# PDU_Schematic.net
KiCad netlist of a schematic drawn in Altium Designer
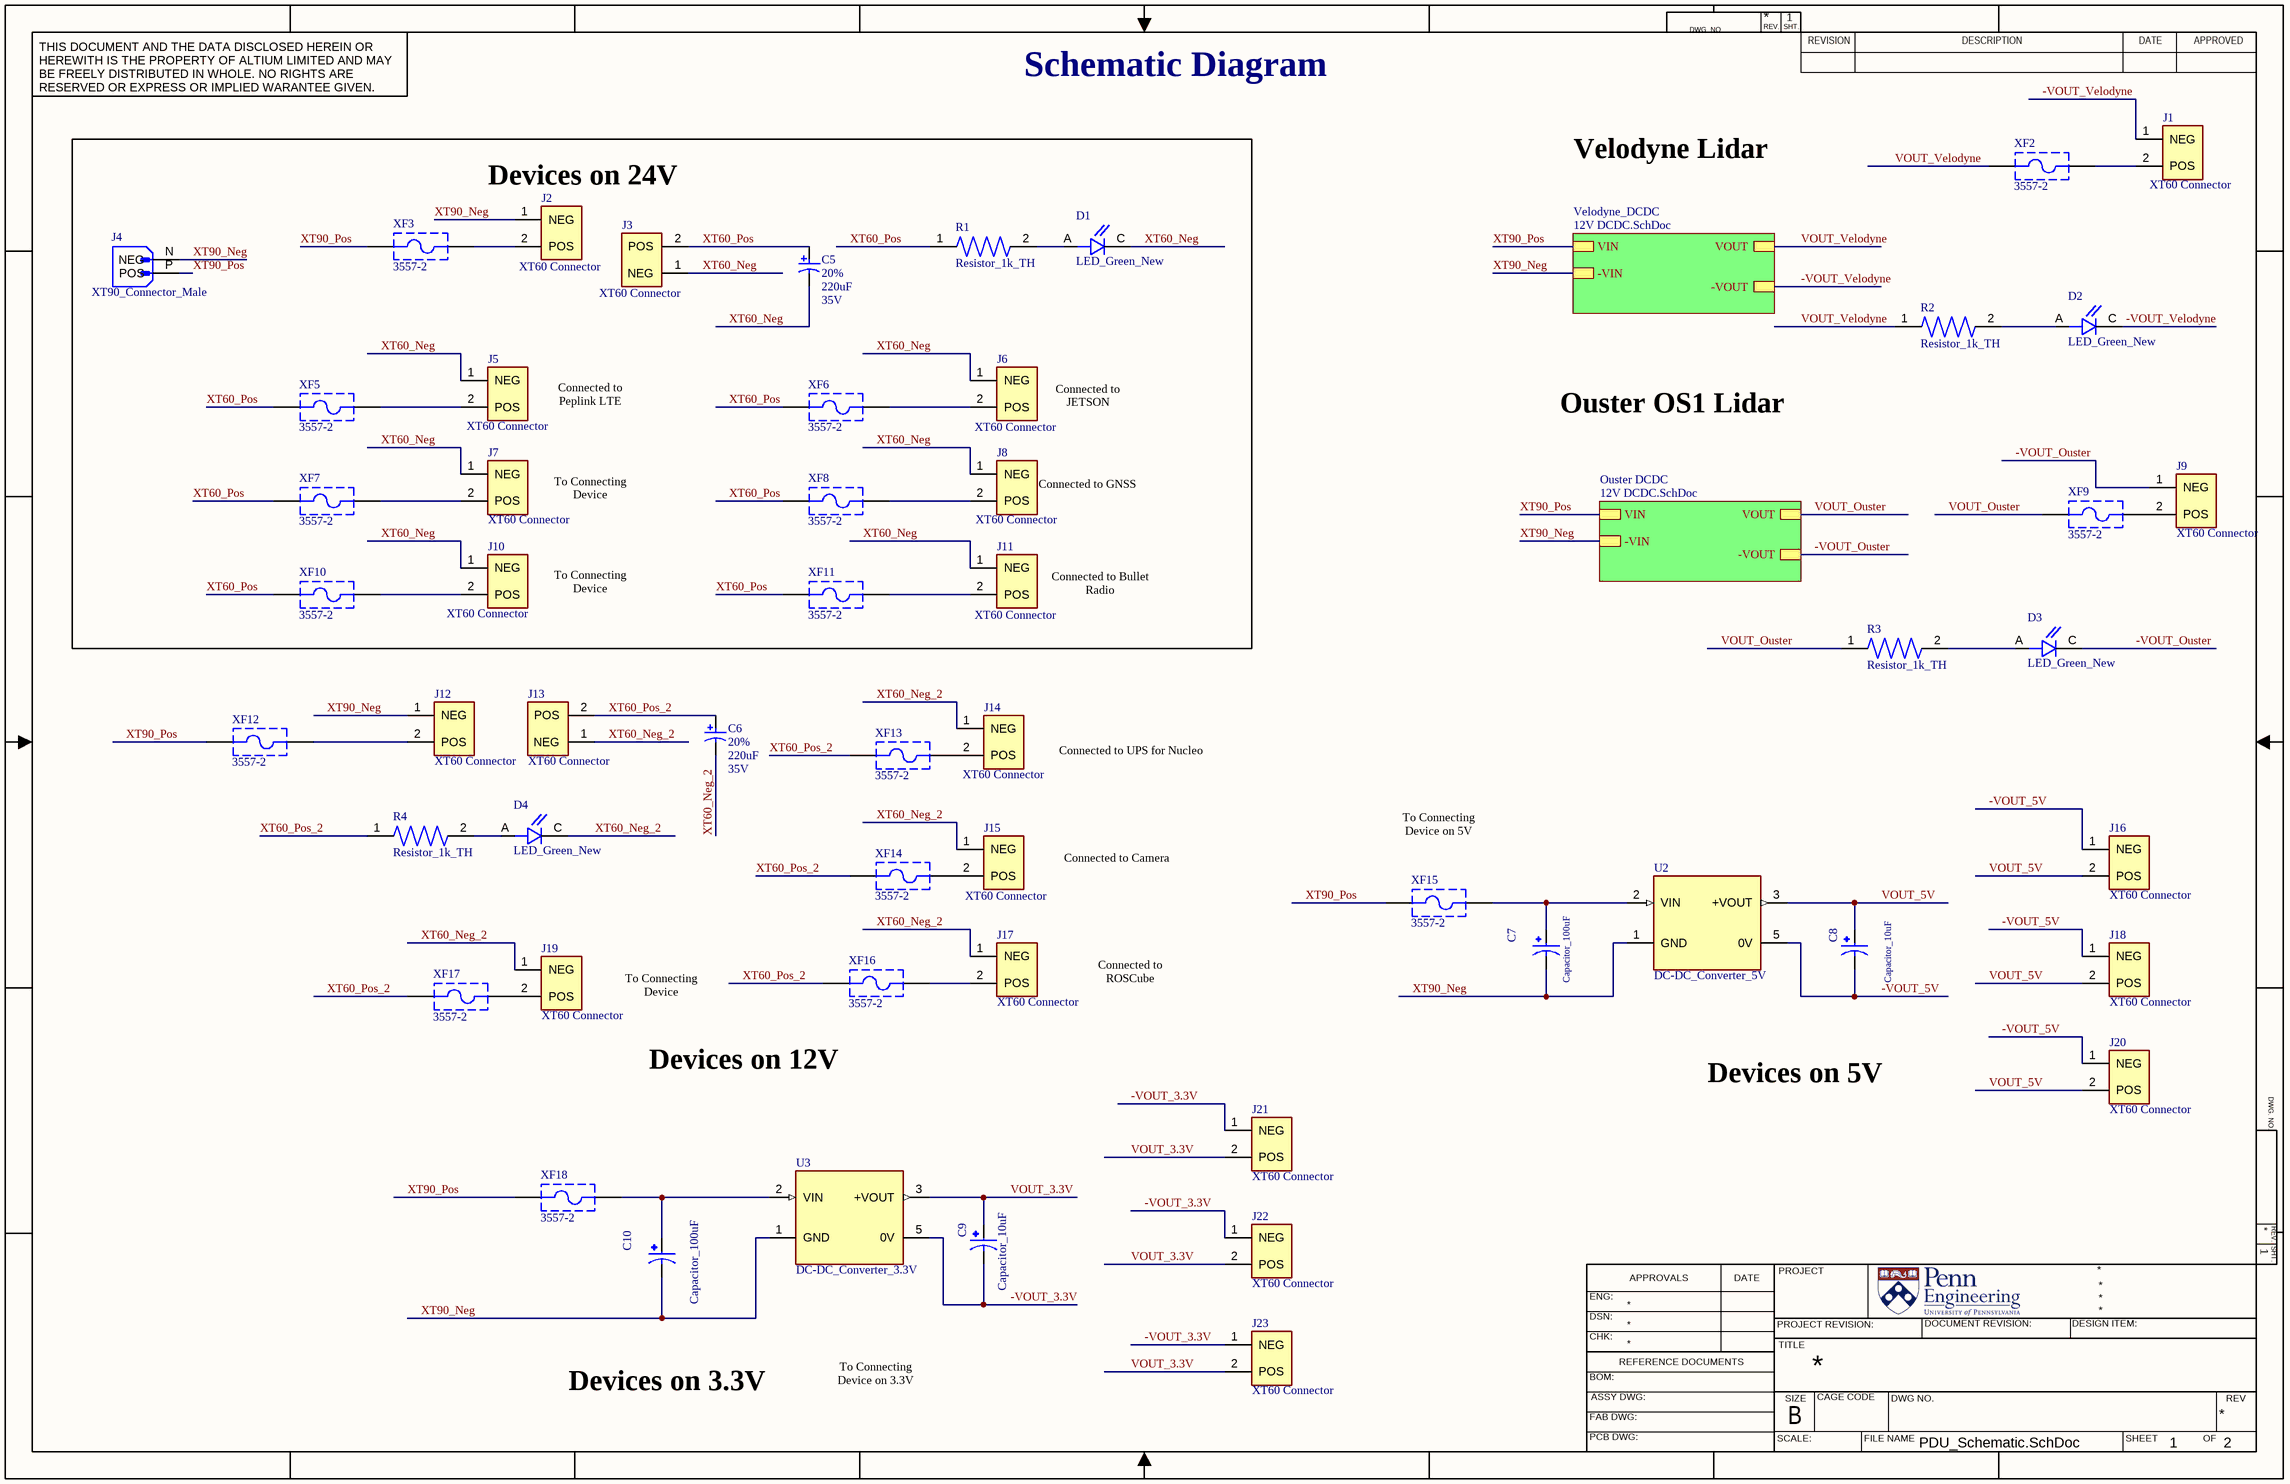
[diagram p0: PDU_Schematic.SchDoc]

(export (version "E")
  (design (tool "Eeschema 10.0.6"))
  (components
    (comp (ref "C5")
      (value "220uF")
      (footprint "NicCap_10x12.5")
      (fields
        (field (name "TOLERANCE") "20%")
        (field (name "VOLTAGE") "35V")
        (field (name "Comment") "ESC227M035AH1AA")
      )
      (libsource (lib "ESE)") (part "NIC-CAP-P-2"))
    )
    (comp (ref "C6")
      (value "220uF")
      (footprint "NicCap_10x12.5")
      (fields
        (field (name "TOLERANCE") "20%")
        (field (name "VOLTAGE") "35V")
        (field (name "Comment") "ESC227M035AH1AA")
      )
      (libsource (lib "ESE)") (part "NIC-CAP-P-2"))
    )
    (comp (ref "C7")
      (value "Capacitor_100uF")
      (footprint "Capacitor_100uF")
      (description "Cap Aluminum Lytic 100uF 16V 20% (5 X 11mm) Radial 5mm 180mA 2000h 85C Automotive Ammo")
      (fields
        (field (name "MANUFACTURER") "Panasonic")
        (field (name "MANUFACTURER PART NUMBER") "ECA-1CM101B")
      )
      (libsource (lib "Schlib1") (part "Capacitor_100uF"))
    )
    (comp (ref "C8")
      (value "Capacitor_10uF")
      (footprint "Capacitor_10uF")
      (description "Cap Aluminum 10uF 50V 20% (6.3 X 5mm) Radial 2.5mm 35mA 1000 hr 85°C Bulk")
      (fields
        (field (name "MANUFACTURER") "Panasonic")
        (field (name "MANUFACTURER PART NUMBER") "ECE-A1HKS100")
      )
      (libsource (lib "Schlib1") (part "Capacitor_10uF"))
    )
    (comp (ref "C9")
      (value "Capacitor_10uF")
      (footprint "Capacitor_10uF")
      (description "Cap Aluminum 10uF 50V 20% (6.3 X 5mm) Radial 2.5mm 35mA 1000 hr 85°C Bulk")
      (fields
        (field (name "MANUFACTURER") "Panasonic")
        (field (name "MANUFACTURER PART NUMBER") "ECE-A1HKS100")
      )
      (libsource (lib "Schlib1") (part "Capacitor_10uF"))
    )
    (comp (ref "C10")
      (value "Capacitor_100uF")
      (footprint "Capacitor_100uF")
      (description "Cap Aluminum Lytic 100uF 16V 20% (5 X 11mm) Radial 5mm 180mA 2000h 85C Automotive Ammo")
      (fields
        (field (name "MANUFACTURER") "Panasonic")
        (field (name "MANUFACTURER PART NUMBER") "ECA-1CM101B")
      )
      (libsource (lib "Schlib1") (part "Capacitor_100uF"))
    )
    (comp (ref "D1")
      (value "LED_Green_New")
      (footprint "LED_Green_New")
      (description "White high-intensity LED lamp, Color White, Vf 3.2 V, Radial-2, RoHS")
      (fields (field (name "MANUFACTURER") "TT Optek") (field (name "MANUFACTURER PART NUMBER") "OVLAW4CB7"))
      (libsource (lib "Schlib1") (part "LED_Green_New"))
    )
    (comp (ref "D2")
      (value "LED_Green_New")
      (footprint "LED_Green_New")
      (description "White high-intensity LED lamp, Color White, Vf 3.2 V, Radial-2, RoHS")
      (fields (field (name "MANUFACTURER") "TT Optek") (field (name "MANUFACTURER PART NUMBER") "OVLAW4CB7"))
      (libsource (lib "Schlib1") (part "LED_Green_New"))
    )
    (comp (ref "D3")
      (value "LED_Green_New")
      (footprint "LED_Green_New")
      (description "White high-intensity LED lamp, Color White, Vf 3.2 V, Radial-2, RoHS")
      (fields (field (name "MANUFACTURER") "TT Optek") (field (name "MANUFACTURER PART NUMBER") "OVLAW4CB7"))
      (libsource (lib "Schlib1") (part "LED_Green_New"))
    )
    (comp (ref "D4")
      (value "LED_Green_New")
      (footprint "LED_Green_New")
      (description "White high-intensity LED lamp, Color White, Vf 3.2 V, Radial-2, RoHS")
      (fields (field (name "MANUFACTURER") "TT Optek") (field (name "MANUFACTURER PART NUMBER") "OVLAW4CB7"))
      (libsource (lib "Schlib1") (part "LED_Green_New"))
    )
    (comp (ref "J1")
      (value "XT60 Connector")
      (footprint "XT60_Connector")
      (description "DC power connectors AMASS - XT60")
      (libsource (lib "Schlib1") (part "XT60 Connector"))
    )
    (comp (ref "J2")
      (value "XT60 Connector")
      (footprint "XT60_Connector")
      (description "DC power connectors AMASS - XT60")
      (libsource (lib "Schlib1") (part "XT60 Connector"))
    )
    (comp (ref "J3")
      (value "XT60 Connector")
      (footprint "XT60_Connector")
      (description "DC power connectors AMASS - XT60")
      (libsource (lib "") (part "XT60 Connector_1"))
    )
    (comp (ref "J4")
      (value "XT90_Connector_Male")
      (footprint "XT90_Connector_Male")
      (description "DC power connectors AMASS - XT90")
      (libsource (lib "Schlib1") (part "XT90_Connector_Male"))
    )
    (comp (ref "J5")
      (value "XT60 Connector")
      (footprint "XT60_Connector")
      (description "DC power connectors AMASS - XT60")
      (libsource (lib "Schlib1") (part "XT60 Connector"))
    )
    (comp (ref "J6")
      (value "XT60 Connector")
      (footprint "XT60_Connector")
      (description "DC power connectors AMASS - XT60")
      (libsource (lib "Schlib1") (part "XT60 Connector"))
    )
    (comp (ref "J7")
      (value "XT60 Connector")
      (footprint "XT60_Connector")
      (description "DC power connectors AMASS - XT60")
      (libsource (lib "Schlib1") (part "XT60 Connector"))
    )
    (comp (ref "J8")
      (value "XT60 Connector")
      (footprint "XT60_Connector")
      (description "DC power connectors AMASS - XT60")
      (libsource (lib "Schlib1") (part "XT60 Connector"))
    )
    (comp (ref "J9")
      (value "XT60 Connector")
      (footprint "XT60_Connector")
      (description "DC power connectors AMASS - XT60")
      (libsource (lib "Schlib1") (part "XT60 Connector"))
    )
    (comp (ref "J10")
      (value "XT60 Connector")
      (footprint "XT60_Connector")
      (description "DC power connectors AMASS - XT60")
      (libsource (lib "Schlib1") (part "XT60 Connector"))
    )
    (comp (ref "J11")
      (value "XT60 Connector")
      (footprint "XT60_Connector")
      (description "DC power connectors AMASS - XT60")
      (libsource (lib "Schlib1") (part "XT60 Connector"))
    )
    (comp (ref "J12")
      (value "XT60 Connector")
      (footprint "XT60_Connector")
      (description "DC power connectors AMASS - XT60")
      (libsource (lib "Schlib1") (part "XT60 Connector"))
    )
    (comp (ref "J13")
      (value "XT60 Connector")
      (footprint "XT60_Connector")
      (description "DC power connectors AMASS - XT60")
      (libsource (lib "") (part "XT60 Connector_1"))
    )
    (comp (ref "J14")
      (value "XT60 Connector")
      (footprint "XT60_Connector")
      (description "DC power connectors AMASS - XT60")
      (libsource (lib "Schlib1") (part "XT60 Connector"))
    )
    (comp (ref "J15")
      (value "XT60 Connector")
      (footprint "XT60_Connector")
      (description "DC power connectors AMASS - XT60")
      (libsource (lib "Schlib1") (part "XT60 Connector"))
    )
    (comp (ref "J16")
      (value "XT60 Connector")
      (footprint "XT60_Connector")
      (description "DC power connectors AMASS - XT60")
      (libsource (lib "Schlib1") (part "XT60 Connector"))
    )
    (comp (ref "J17")
      (value "XT60 Connector")
      (footprint "XT60_Connector")
      (description "DC power connectors AMASS - XT60")
      (libsource (lib "Schlib1") (part "XT60 Connector"))
    )
    (comp (ref "J18")
      (value "XT60 Connector")
      (footprint "XT60_Connector")
      (description "DC power connectors AMASS - XT60")
      (libsource (lib "Schlib1") (part "XT60 Connector"))
    )
    (comp (ref "J19")
      (value "XT60 Connector")
      (footprint "XT60_Connector")
      (description "DC power connectors AMASS - XT60")
      (libsource (lib "Schlib1") (part "XT60 Connector"))
    )
    (comp (ref "J20")
      (value "XT60 Connector")
      (footprint "XT60_Connector")
      (description "DC power connectors AMASS - XT60")
      (libsource (lib "Schlib1") (part "XT60 Connector"))
    )
    (comp (ref "J21")
      (value "XT60 Connector")
      (footprint "XT60_Connector")
      (description "DC power connectors AMASS - XT60")
      (libsource (lib "Schlib1") (part "XT60 Connector"))
    )
    (comp (ref "J22")
      (value "XT60 Connector")
      (footprint "XT60_Connector")
      (description "DC power connectors AMASS - XT60")
      (libsource (lib "Schlib1") (part "XT60 Connector"))
    )
    (comp (ref "J23")
      (value "XT60 Connector")
      (footprint "XT60_Connector")
      (description "DC power connectors AMASS - XT60")
      (libsource (lib "Schlib1") (part "XT60 Connector"))
    )
    (comp (ref "R1")
      (value "Resistor_1k_TH")
      (footprint "Resistor_1k_TH")
      (description "Carbon Film Resistors - Through Hole 1K Ohm 5% 1/4W Res Carbon Film")
      (fields
        (field (name "MANUFACTURER") "TE Connectivity")
        (field (name "MANUFACTURER PART NUMBER") "2-1623927-3")
      )
      (libsource (lib "Schlib1") (part "Resistor_1k_TH"))
    )
    (comp (ref "R2")
      (value "Resistor_1k_TH")
      (footprint "Resistor_1k_TH")
      (description "Carbon Film Resistors - Through Hole 1K Ohm 5% 1/4W Res Carbon Film")
      (fields
        (field (name "MANUFACTURER") "TE Connectivity")
        (field (name "MANUFACTURER PART NUMBER") "2-1623927-3")
      )
      (libsource (lib "Schlib1") (part "Resistor_1k_TH"))
    )
    (comp (ref "R3")
      (value "Resistor_1k_TH")
      (footprint "Resistor_1k_TH")
      (description "Carbon Film Resistors - Through Hole 1K Ohm 5% 1/4W Res Carbon Film")
      (fields
        (field (name "MANUFACTURER") "TE Connectivity")
        (field (name "MANUFACTURER PART NUMBER") "2-1623927-3")
      )
      (libsource (lib "Schlib1") (part "Resistor_1k_TH"))
    )
    (comp (ref "R4")
      (value "Resistor_1k_TH")
      (footprint "Resistor_1k_TH")
      (description "Carbon Film Resistors - Through Hole 1K Ohm 5% 1/4W Res Carbon Film")
      (fields
        (field (name "MANUFACTURER") "TE Connectivity")
        (field (name "MANUFACTURER PART NUMBER") "2-1623927-3")
      )
      (libsource (lib "Schlib1") (part "Resistor_1k_TH"))
    )
    (comp (ref "U2")
      (value "DC-DC_Converter_5V")
      (footprint "DC-DC_Converter_5V")
      (description "5 Vdc, 2 A, 10 W, 8 to 36 Vdc Input Range")
      (fields (field (name "MANUFACTURER") "CUI") (field (name "MANUFACTURER PART NUMBER") "P7805-2000R-S"))
      (libsource (lib "Schlib1") (part "DC-DC_Converter_5V"))
    )
    (comp (ref "U3")
      (value "DC-DC_Converter_3.3V")
      (footprint "DC-DC_Converter_3.3V")
      (description "3.3 Vdc, 2 A, 6.6 W, 6 to 36 Vdc Input Range")
      (fields (field (name "MANUFACTURER") "CUI") (field (name "MANUFACTURER PART NUMBER") "P7803-2000R-S"))
      (libsource (lib "Schlib1") (part "DC-DC_Converter_3.3V"))
    )
    (comp (ref "XF2")
      (value "3557-2")
      (footprint "KSTN-3557-2")
      (description "Fuse Holder; Auto; 2 in1 Blade; THM; 1 Fuse; Vertical; 30 Amps; ATO/ATC")
      (libsource (lib "ESE)") (part "FUSE_HOLDER-4"))
    )
    (comp (ref "XF3")
      (value "3557-2")
      (footprint "KSTN-3557-2")
      (description "Fuse Holder; Auto; 2 in1 Blade; THM; 1 Fuse; Vertical; 30 Amps; ATO/ATC")
      (libsource (lib "ESE)") (part "FUSE_HOLDER-4"))
    )
    (comp (ref "XF5")
      (value "3557-2")
      (footprint "KSTN-3557-2")
      (description "Fuse Holder; Auto; 2 in1 Blade; THM; 1 Fuse; Vertical; 30 Amps; ATO/ATC")
      (libsource (lib "ESE)") (part "FUSE_HOLDER-4"))
    )
    (comp (ref "XF6")
      (value "3557-2")
      (footprint "KSTN-3557-2")
      (description "Fuse Holder; Auto; 2 in1 Blade; THM; 1 Fuse; Vertical; 30 Amps; ATO/ATC")
      (libsource (lib "ESE)") (part "FUSE_HOLDER-4"))
    )
    (comp (ref "XF7")
      (value "3557-2")
      (footprint "KSTN-3557-2")
      (description "Fuse Holder; Auto; 2 in1 Blade; THM; 1 Fuse; Vertical; 30 Amps; ATO/ATC")
      (libsource (lib "ESE)") (part "FUSE_HOLDER-4"))
    )
    (comp (ref "XF8")
      (value "3557-2")
      (footprint "KSTN-3557-2")
      (description "Fuse Holder; Auto; 2 in1 Blade; THM; 1 Fuse; Vertical; 30 Amps; ATO/ATC")
      (libsource (lib "ESE)") (part "FUSE_HOLDER-4"))
    )
    (comp (ref "XF9")
      (value "3557-2")
      (footprint "KSTN-3557-2")
      (description "Fuse Holder; Auto; 2 in1 Blade; THM; 1 Fuse; Vertical; 30 Amps; ATO/ATC")
      (libsource (lib "ESE)") (part "FUSE_HOLDER-4"))
    )
    (comp (ref "XF10")
      (value "3557-2")
      (footprint "KSTN-3557-2")
      (description "Fuse Holder; Auto; 2 in1 Blade; THM; 1 Fuse; Vertical; 30 Amps; ATO/ATC")
      (libsource (lib "ESE)") (part "FUSE_HOLDER-4"))
    )
    (comp (ref "XF11")
      (value "3557-2")
      (footprint "KSTN-3557-2")
      (description "Fuse Holder; Auto; 2 in1 Blade; THM; 1 Fuse; Vertical; 30 Amps; ATO/ATC")
      (libsource (lib "ESE)") (part "FUSE_HOLDER-4"))
    )
    (comp (ref "XF12")
      (value "3557-2")
      (footprint "KSTN-3557-2")
      (description "Fuse Holder; Auto; 2 in1 Blade; THM; 1 Fuse; Vertical; 30 Amps; ATO/ATC")
      (libsource (lib "ESE)") (part "FUSE_HOLDER-4"))
    )
    (comp (ref "XF13")
      (value "3557-2")
      (footprint "KSTN-3557-2")
      (description "Fuse Holder; Auto; 2 in1 Blade; THM; 1 Fuse; Vertical; 30 Amps; ATO/ATC")
      (libsource (lib "ESE)") (part "FUSE_HOLDER-4"))
    )
    (comp (ref "XF14")
      (value "3557-2")
      (footprint "KSTN-3557-2")
      (description "Fuse Holder; Auto; 2 in1 Blade; THM; 1 Fuse; Vertical; 30 Amps; ATO/ATC")
      (libsource (lib "ESE)") (part "FUSE_HOLDER-4"))
    )
    (comp (ref "XF15")
      (value "3557-2")
      (footprint "KSTN-3557-2")
      (description "Fuse Holder; Auto; 2 in1 Blade; THM; 1 Fuse; Vertical; 30 Amps; ATO/ATC")
      (libsource (lib "University of Pennsylvania (SEAS)") (part "FUSE_HOLDER-4"))
    )
    (comp (ref "XF16")
      (value "3557-2")
      (footprint "KSTN-3557-2")
      (description "Fuse Holder; Auto; 2 in1 Blade; THM; 1 Fuse; Vertical; 30 Amps; ATO/ATC")
      (libsource (lib "University of Pennsylvania (SEAS)") (part "FUSE_HOLDER-4"))
    )
    (comp (ref "XF17")
      (value "3557-2")
      (footprint "KSTN-3557-2")
      (description "Fuse Holder; Auto; 2 in1 Blade; THM; 1 Fuse; Vertical; 30 Amps; ATO/ATC")
      (libsource (lib "ESE)") (part "FUSE_HOLDER-4"))
    )
    (comp (ref "XF18")
      (value "3557-2")
      (footprint "KSTN-3557-2")
      (description "Fuse Holder; Auto; 2 in1 Blade; THM; 1 Fuse; Vertical; 30 Amps; ATO/ATC")
      (libsource (lib "University of Pennsylvania (SEAS)") (part "FUSE_HOLDER-4"))
    )
  )
  (nets
    (net (code "1") (name "/-VOUT_3.3V") (class "Default")
      (node (ref "C9") (pin "N") (pinfunction "N_N") (pintype "passive"))
      (node (ref "J21") (pin "1") (pinfunction "NEG_1") (pintype "passive"))
      (node (ref "J22") (pin "1") (pinfunction "NEG_1") (pintype "passive"))
      (node (ref "J23") (pin "1") (pinfunction "NEG_1") (pintype "passive"))
      (node (ref "U3") (pin "5") (pinfunction "0V_5") (pintype "power_in"))
    )
    (net (code "2") (name "/-VOUT_5V") (class "Default")
      (node (ref "C8") (pin "N") (pinfunction "N_N") (pintype "passive"))
      (node (ref "J16") (pin "1") (pinfunction "NEG_1") (pintype "passive"))
      (node (ref "J18") (pin "1") (pinfunction "NEG_1") (pintype "passive"))
      (node (ref "J20") (pin "1") (pinfunction "NEG_1") (pintype "passive"))
      (node (ref "U2") (pin "5") (pinfunction "0V_5") (pintype "power_in"))
    )
    (net (code "3") (name "/-VOUT_Ouster") (class "Default")
      (node (ref "D3") (pin "C") (pinfunction "C_C") (pintype "passive"))
      (node (ref "J9") (pin "1") (pinfunction "NEG_1") (pintype "passive"))
    )
    (net (code "4") (name "/-VOUT_Velodyne") (class "Default")
      (node (ref "D2") (pin "C") (pinfunction "C_C") (pintype "passive"))
      (node (ref "J1") (pin "1") (pinfunction "NEG_1") (pintype "passive"))
    )
    (net (code "5") (name "/VOUT_3.3V") (class "Default")
      (node (ref "C9") (pin "P") (pinfunction "P_P") (pintype "passive"))
      (node (ref "J21") (pin "2") (pinfunction "POS_2") (pintype "passive"))
      (node (ref "J22") (pin "2") (pinfunction "POS_2") (pintype "passive"))
      (node (ref "J23") (pin "2") (pinfunction "POS_2") (pintype "passive"))
      (node (ref "U3") (pin "3") (pinfunction "+VOUT_3") (pintype "output"))
    )
    (net (code "6") (name "/VOUT_5V") (class "Default")
      (node (ref "C8") (pin "P") (pinfunction "P_P") (pintype "passive"))
      (node (ref "J16") (pin "2") (pinfunction "POS_2") (pintype "passive"))
      (node (ref "J18") (pin "2") (pinfunction "POS_2") (pintype "passive"))
      (node (ref "J20") (pin "2") (pinfunction "POS_2") (pintype "passive"))
      (node (ref "U2") (pin "3") (pinfunction "+VOUT_3") (pintype "output"))
    )
    (net (code "7") (name "/VOUT_Ouster") (class "Default")
      (node (ref "R3") (pin "1") (pinfunction "1_1") (pintype "passive"))
      (node (ref "XF9") (pin "1") (pinfunction "1_1") (pintype "passive"))
    )
    (net (code "8") (name "/VOUT_Velodyne") (class "Default")
      (node (ref "R2") (pin "1") (pinfunction "1_1") (pintype "passive"))
      (node (ref "XF2") (pin "1") (pinfunction "1_1") (pintype "passive"))
    )
    (net (code "9") (name "/XT60_Neg") (class "Default")
      (node (ref "C5") (pin "2") (pinfunction "2_2") (pintype "passive"))
      (node (ref "D1") (pin "C") (pinfunction "C_C") (pintype "passive"))
      (node (ref "J10") (pin "1") (pinfunction "NEG_1") (pintype "passive"))
      (node (ref "J11") (pin "1") (pinfunction "NEG_1") (pintype "passive"))
      (node (ref "J3") (pin "1") (pinfunction "NEG_1") (pintype "passive"))
      (node (ref "J5") (pin "1") (pinfunction "NEG_1") (pintype "passive"))
      (node (ref "J6") (pin "1") (pinfunction "NEG_1") (pintype "passive"))
      (node (ref "J7") (pin "1") (pinfunction "NEG_1") (pintype "passive"))
      (node (ref "J8") (pin "1") (pinfunction "NEG_1") (pintype "passive"))
    )
    (net (code "10") (name "/XT60_Neg_2") (class "Default")
      (node (ref "C6") (pin "2") (pinfunction "2_2") (pintype "passive"))
      (node (ref "D4") (pin "C") (pinfunction "C_C") (pintype "passive"))
      (node (ref "J13") (pin "1") (pinfunction "NEG_1") (pintype "passive"))
      (node (ref "J14") (pin "1") (pinfunction "NEG_1") (pintype "passive"))
      (node (ref "J15") (pin "1") (pinfunction "NEG_1") (pintype "passive"))
      (node (ref "J17") (pin "1") (pinfunction "NEG_1") (pintype "passive"))
      (node (ref "J19") (pin "1") (pinfunction "NEG_1") (pintype "passive"))
    )
    (net (code "11") (name "/XT60_Pos") (class "Default")
      (node (ref "C5") (pin "1") (pinfunction "1_1") (pintype "passive"))
      (node (ref "J3") (pin "2") (pinfunction "POS_2") (pintype "passive"))
      (node (ref "R1") (pin "1") (pinfunction "1_1") (pintype "passive"))
      (node (ref "XF10") (pin "1") (pinfunction "1_1") (pintype "passive"))
      (node (ref "XF11") (pin "1") (pinfunction "1_1") (pintype "passive"))
      (node (ref "XF5") (pin "1") (pinfunction "1_1") (pintype "passive"))
      (node (ref "XF6") (pin "1") (pinfunction "1_1") (pintype "passive"))
      (node (ref "XF7") (pin "1") (pinfunction "1_1") (pintype "passive"))
      (node (ref "XF8") (pin "1") (pinfunction "1_1") (pintype "passive"))
    )
    (net (code "12") (name "/XT60_Pos_2") (class "Default")
      (node (ref "C6") (pin "1") (pinfunction "1_1") (pintype "passive"))
      (node (ref "J13") (pin "2") (pinfunction "POS_2") (pintype "passive"))
      (node (ref "R4") (pin "1") (pinfunction "1_1") (pintype "passive"))
      (node (ref "XF13") (pin "1") (pinfunction "1_1") (pintype "passive"))
      (node (ref "XF14") (pin "1") (pinfunction "1_1") (pintype "passive"))
      (node (ref "XF16") (pin "1") (pinfunction "1_1") (pintype "passive"))
      (node (ref "XF17") (pin "1") (pinfunction "1_1") (pintype "passive"))
    )
    (net (code "13") (name "/XT90_Neg") (class "Default")
      (node (ref "C10") (pin "N") (pinfunction "N_N") (pintype "passive"))
      (node (ref "C7") (pin "N") (pinfunction "N_N") (pintype "passive"))
      (node (ref "J12") (pin "1") (pinfunction "NEG_1") (pintype "passive"))
      (node (ref "J2") (pin "1") (pinfunction "NEG_1") (pintype "passive"))
      (node (ref "J4") (pin "N") (pinfunction "NEG_N") (pintype "passive"))
      (node (ref "U2") (pin "1") (pinfunction "GND_1") (pintype "power_in"))
      (node (ref "U3") (pin "1") (pinfunction "GND_1") (pintype "power_in"))
    )
    (net (code "14") (name "/XT90_Pos") (class "Default")
      (node (ref "J4") (pin "P") (pinfunction "POS_P") (pintype "passive"))
      (node (ref "XF12") (pin "1") (pinfunction "1_1") (pintype "passive"))
      (node (ref "XF15") (pin "1") (pinfunction "1_1") (pintype "passive"))
      (node (ref "XF18") (pin "1") (pinfunction "1_1") (pintype "passive"))
      (node (ref "XF3") (pin "1") (pinfunction "1_1") (pintype "passive"))
    )
    (net (code "15") (name "Net-(D1-PadA)") (class "Default")
      (node (ref "D1") (pin "A") (pinfunction "A_A") (pintype "passive"))
      (node (ref "R1") (pin "2") (pinfunction "2_2") (pintype "passive"))
    )
    (net (code "16") (name "Net-(D2-PadA)") (class "Default")
      (node (ref "D2") (pin "A") (pinfunction "A_A") (pintype "passive"))
      (node (ref "R2") (pin "2") (pinfunction "2_2") (pintype "passive"))
    )
    (net (code "17") (name "Net-(D3-PadA)") (class "Default")
      (node (ref "D3") (pin "A") (pinfunction "A_A") (pintype "passive"))
      (node (ref "R3") (pin "2") (pinfunction "2_2") (pintype "passive"))
    )
    (net (code "18") (name "Net-(D4-PadA)") (class "Default")
      (node (ref "D4") (pin "A") (pinfunction "A_A") (pintype "passive"))
      (node (ref "R4") (pin "2") (pinfunction "2_2") (pintype "passive"))
    )
    (net (code "19") (name "Net-(J1-POS)") (class "Default")
      (node (ref "J1") (pin "2") (pinfunction "POS_2") (pintype "passive"))
      (node (ref "XF2") (pin "2") (pinfunction "2_2") (pintype "passive"))
    )
    (net (code "20") (name "Net-(J2-POS)") (class "Default")
      (node (ref "J2") (pin "2") (pinfunction "POS_2") (pintype "passive"))
      (node (ref "XF3") (pin "2") (pinfunction "2_2") (pintype "passive"))
    )
    (net (code "21") (name "Net-(J5-POS)") (class "Default")
      (node (ref "J5") (pin "2") (pinfunction "POS_2") (pintype "passive"))
      (node (ref "XF5") (pin "2") (pinfunction "2_2") (pintype "passive"))
    )
    (net (code "22") (name "Net-(J6-POS)") (class "Default")
      (node (ref "J6") (pin "2") (pinfunction "POS_2") (pintype "passive"))
      (node (ref "XF6") (pin "2") (pinfunction "2_2") (pintype "passive"))
    )
    (net (code "23") (name "Net-(J7-POS)") (class "Default")
      (node (ref "J7") (pin "2") (pinfunction "POS_2") (pintype "passive"))
      (node (ref "XF7") (pin "2") (pinfunction "2_2") (pintype "passive"))
    )
    (net (code "24") (name "Net-(J8-POS)") (class "Default")
      (node (ref "J8") (pin "2") (pinfunction "POS_2") (pintype "passive"))
      (node (ref "XF8") (pin "2") (pinfunction "2_2") (pintype "passive"))
    )
    (net (code "25") (name "Net-(J9-POS)") (class "Default")
      (node (ref "J9") (pin "2") (pinfunction "POS_2") (pintype "passive"))
      (node (ref "XF9") (pin "2") (pinfunction "2_2") (pintype "passive"))
    )
    (net (code "26") (name "Net-(J10-POS)") (class "Default")
      (node (ref "J10") (pin "2") (pinfunction "POS_2") (pintype "passive"))
      (node (ref "XF10") (pin "2") (pinfunction "2_2") (pintype "passive"))
    )
    (net (code "27") (name "Net-(J11-POS)") (class "Default")
      (node (ref "J11") (pin "2") (pinfunction "POS_2") (pintype "passive"))
      (node (ref "XF11") (pin "2") (pinfunction "2_2") (pintype "passive"))
    )
    (net (code "28") (name "Net-(J12-POS)") (class "Default")
      (node (ref "J12") (pin "2") (pinfunction "POS_2") (pintype "passive"))
      (node (ref "XF12") (pin "2") (pinfunction "2_2") (pintype "passive"))
    )
    (net (code "29") (name "Net-(J14-POS)") (class "Default")
      (node (ref "J14") (pin "2") (pinfunction "POS_2") (pintype "passive"))
      (node (ref "XF13") (pin "2") (pinfunction "2_2") (pintype "passive"))
    )
    (net (code "30") (name "Net-(J15-POS)") (class "Default")
      (node (ref "J15") (pin "2") (pinfunction "POS_2") (pintype "passive"))
      (node (ref "XF14") (pin "2") (pinfunction "2_2") (pintype "passive"))
    )
    (net (code "31") (name "Net-(J17-POS)") (class "Default")
      (node (ref "J17") (pin "2") (pinfunction "POS_2") (pintype "passive"))
      (node (ref "XF16") (pin "2") (pinfunction "2_2") (pintype "passive"))
    )
    (net (code "32") (name "Net-(J19-POS)") (class "Default")
      (node (ref "J19") (pin "2") (pinfunction "POS_2") (pintype "passive"))
      (node (ref "XF17") (pin "2") (pinfunction "2_2") (pintype "passive"))
    )
    (net (code "33") (name "Net-(U2-VIN)") (class "Default")
      (node (ref "C7") (pin "P") (pinfunction "P_P") (pintype "passive"))
      (node (ref "U2") (pin "2") (pinfunction "VIN_2") (pintype "input"))
      (node (ref "XF15") (pin "2") (pinfunction "2_2") (pintype "passive"))
    )
    (net (code "34") (name "Net-(U3-VIN)") (class "Default")
      (node (ref "C10") (pin "P") (pinfunction "P_P") (pintype "passive"))
      (node (ref "U3") (pin "2") (pinfunction "VIN_2") (pintype "input"))
      (node (ref "XF18") (pin "2") (pinfunction "2_2") (pintype "passive"))
    )
  )
)
